# OpenBook.net
KiCad netlist of a schematic drawn in EAGLE
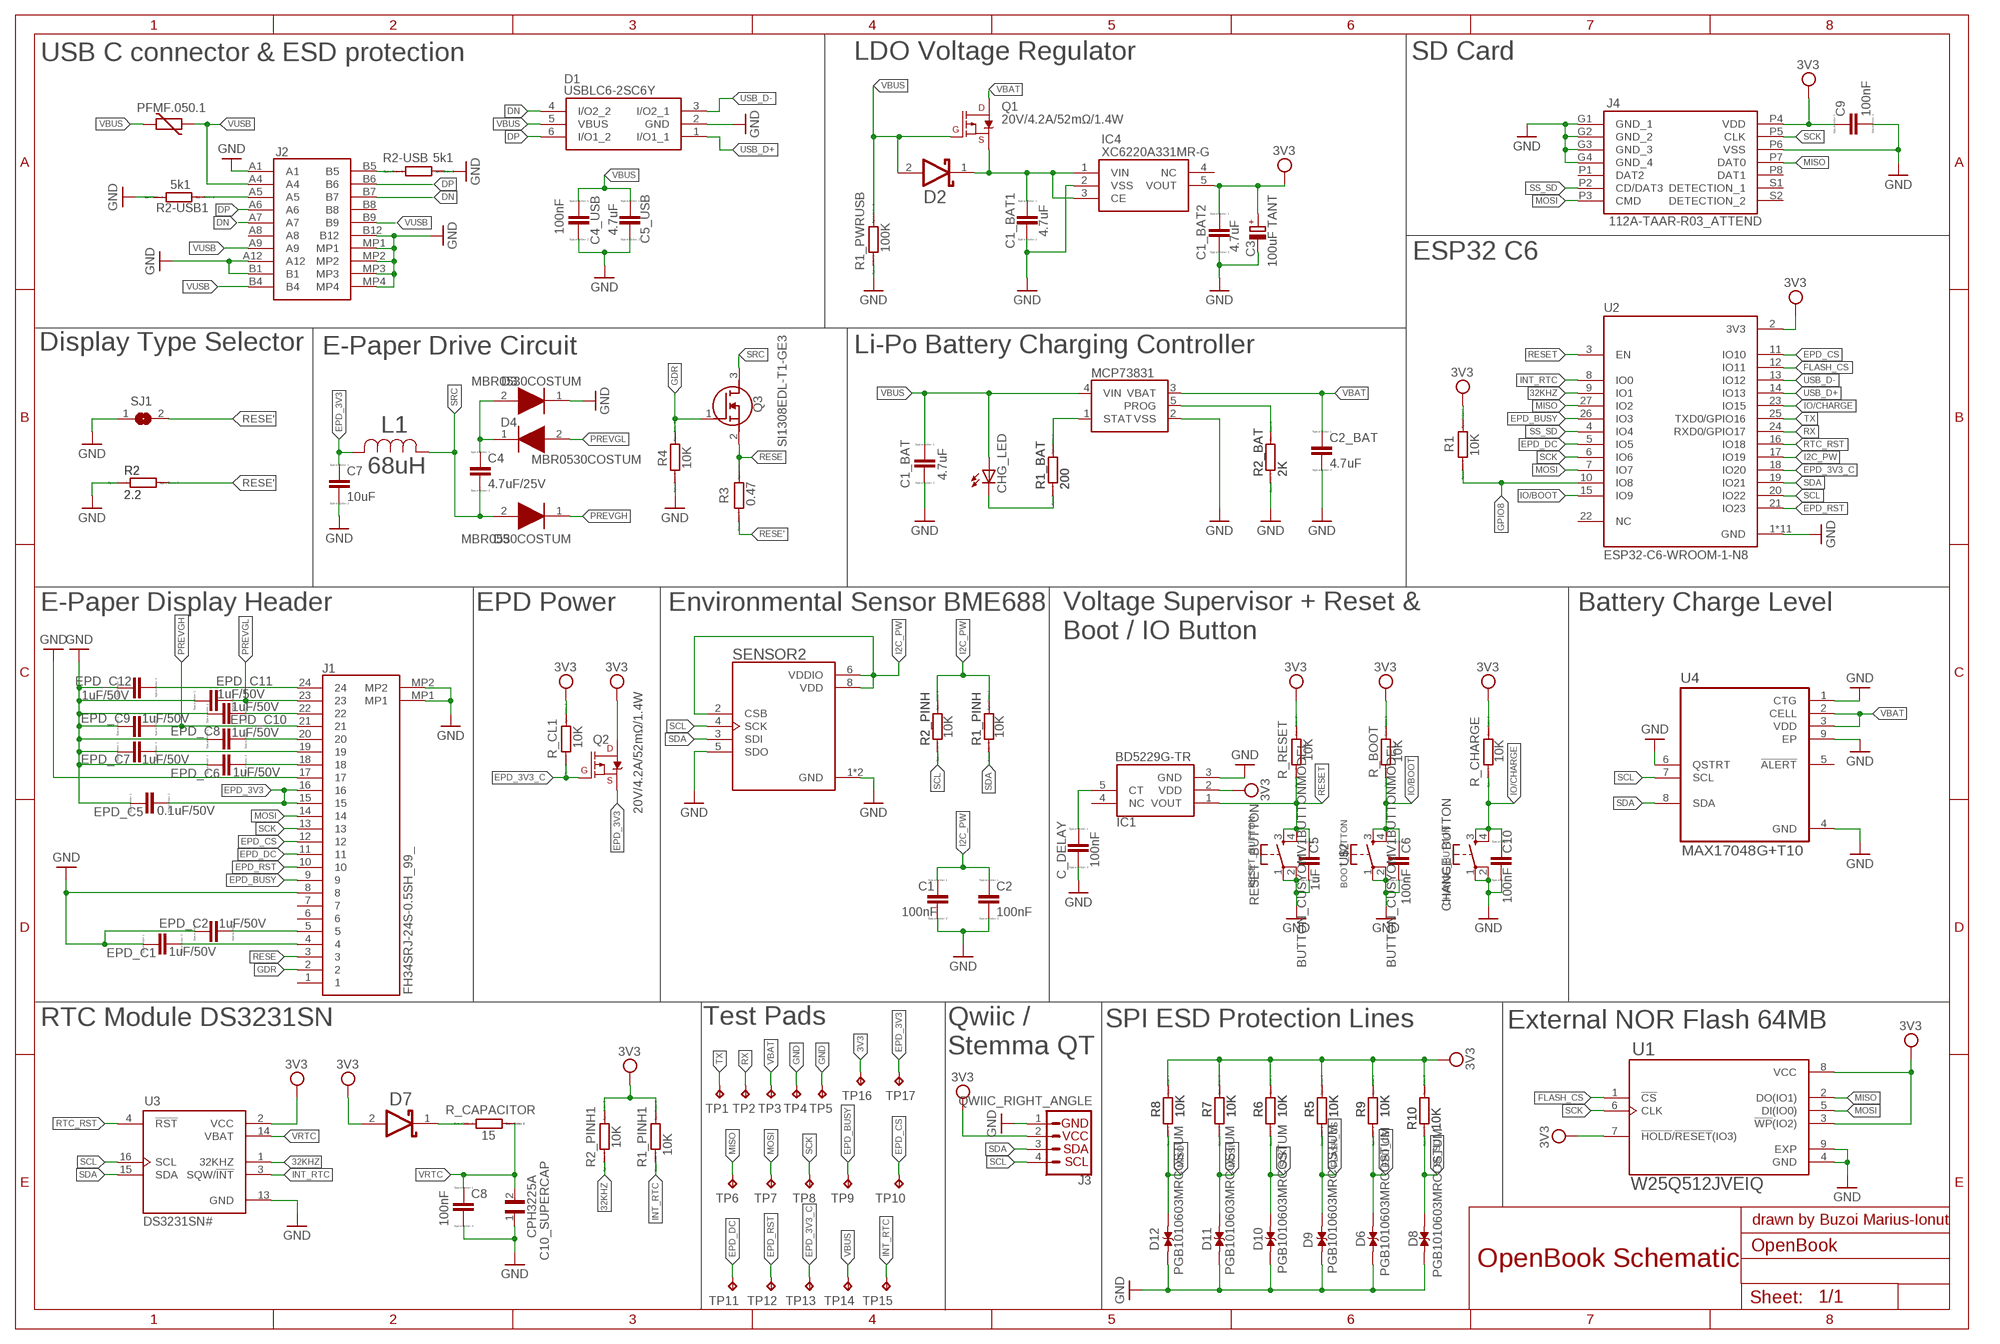
[diagram p0: schematic, sheet 1]

(export (version "E")
  (design (tool "Eeschema 10.0.6"))
  (components
    (comp (ref "C1")
      (value "100nF")
      (footprint "eagle-import:ESP32_WROVER_EAGLE-LTSPICE_C0402")
      (libsource (lib "eagle-import") (part "ESP32_WROVER_EAGLE-LTSPICE_C"))
    )
    (comp (ref "C1_BAT")
      (value "4.7uF")
      (footprint "eagle-import:ESP32_WROVER_EAGLE-LTSPICE_C0402")
      (libsource (lib "eagle-import") (part "ESP32_WROVER_EAGLE-LTSPICE_C"))
    )
    (comp (ref "C1_BAT1")
      (value "4.7uF")
      (footprint "eagle-import:ESP32_WROVER_EAGLE-LTSPICE_C0402")
      (libsource (lib "eagle-import") (part "ESP32_WROVER_EAGLE-LTSPICE_C"))
    )
    (comp (ref "C1_BAT2")
      (value "4.7uF")
      (footprint "eagle-import:ESP32_WROVER_EAGLE-LTSPICE_C0402")
      (libsource (lib "eagle-import") (part "ESP32_WROVER_EAGLE-LTSPICE_C"))
    )
    (comp (ref "C2")
      (value "100nF")
      (footprint "eagle-import:ESP32_WROVER_EAGLE-LTSPICE_C0402")
      (libsource (lib "eagle-import") (part "ESP32_WROVER_EAGLE-LTSPICE_C"))
    )
    (comp (ref "C2_BAT")
      (value "4.7uF")
      (footprint "eagle-import:ESP32_WROVER_EAGLE-LTSPICE_C0402")
      (libsource (lib "eagle-import") (part "ESP32_WROVER_EAGLE-LTSPICE_C"))
    )
    (comp (ref "C3")
      (value "100uF TANT")
      (footprint "eagle-import:RCL_CT3528")
      (libsource (lib "eagle-import") (part "RCL_CPOL-EUCT3528"))
    )
    (comp (ref "C4")
      (value "4.7uF/25V")
      (footprint "eagle-import:ESP32_WROVER_EAGLE-LTSPICE_C0402")
      (libsource (lib "eagle-import") (part "ESP32_WROVER_EAGLE-LTSPICE_C"))
    )
    (comp (ref "C4_USB")
      (value "100nF")
      (footprint "eagle-import:ESP32_WROVER_EAGLE-LTSPICE_C0402")
      (libsource (lib "eagle-import") (part "ESP32_WROVER_EAGLE-LTSPICE_C"))
    )
    (comp (ref "C5")
      (value "1uF")
      (footprint "eagle-import:ESP32_WROVER_EAGLE-LTSPICE_C0402")
      (libsource (lib "eagle-import") (part "ESP32_WROVER_EAGLE-LTSPICE_C"))
    )
    (comp (ref "C5_USB")
      (value "4.7uF")
      (footprint "eagle-import:ESP32_WROVER_EAGLE-LTSPICE_C0402")
      (libsource (lib "eagle-import") (part "ESP32_WROVER_EAGLE-LTSPICE_C"))
    )
    (comp (ref "C6")
      (value "100nF")
      (footprint "eagle-import:ESP32_WROVER_EAGLE-LTSPICE_C0402")
      (libsource (lib "eagle-import") (part "ESP32_WROVER_EAGLE-LTSPICE_C"))
    )
    (comp (ref "C7")
      (value "10uF")
      (footprint "eagle-import:ESP32_WROVER_EAGLE-LTSPICE_C0402")
      (libsource (lib "eagle-import") (part "ESP32_WROVER_EAGLE-LTSPICE_C"))
    )
    (comp (ref "C8")
      (value "100nF")
      (footprint "eagle-import:ESP32_WROVER_EAGLE-LTSPICE_C0402")
      (libsource (lib "eagle-import") (part "ESP32_WROVER_EAGLE-LTSPICE_C"))
    )
    (comp (ref "C9")
      (value "100nF")
      (footprint "eagle-import:ESP32_WROVER_EAGLE-LTSPICE_C0402")
      (libsource (lib "eagle-import") (part "ESP32_WROVER_EAGLE-LTSPICE_C"))
    )
    (comp (ref "C10")
      (value "100nF")
      (footprint "eagle-import:ESP32_WROVER_EAGLE-LTSPICE_C0402")
      (libsource (lib "eagle-import") (part "ESP32_WROVER_EAGLE-LTSPICE_C"))
    )
    (comp (ref "C10_SUPERCAP")
      (value "CPH3225A")
      (footprint "eagle-import:CAPCP3225X100N")
      (fields (field (name "MF") "Seiko Instruments"))
      (libsource (lib "eagle-import") (part "CPH3225A"))
    )
    (comp (ref "CHANGE_BUTTON")
      (value "BUTTON_CUSYOMV1BUTTONMODEL")
      (footprint "eagle-import:MYBUTTON")
      (libsource (lib "eagle-import") (part "BUTTON_CUSYOMV1BUTTONMODEL"))
    )
    (comp (ref "CHG_LED")
      (value "ADAFRUIT_LEDCHIP-LED0603")
      (footprint "eagle-import:ADAFRUIT_CHIP-LED0603")
      (libsource (lib "eagle-import") (part "ADAFRUIT_LEDCHIP-LED0603"))
    )
    (comp (ref "C_DELAY")
      (value "100nF")
      (footprint "eagle-import:ESP32_WROVER_EAGLE-LTSPICE_C0402")
      (libsource (lib "eagle-import") (part "ESP32_WROVER_EAGLE-LTSPICE_C"))
    )
    (comp (ref "D1")
      (value "USBLC6-2SC6Y")
      (footprint "eagle-import:SOT95P280X145-6N")
      (fields (field (name "MF") "STMicroelectronics"))
      (libsource (lib "eagle-import") (part "USBLC6-2SC6Y"))
    )
    (comp (ref "D2")
      (value "ESP32_WROVER_AVX---SD0805S020S1R0_AVX_SD0805S020S1R0_0_0AVX_SD0805S020S1R0_0_0")
      (footprint "eagle-import:ESP32_WROVER_AVX---SD0805S020S1R0_AVX_SD0805S020S1R0_0")
      (fields
        (field (name "DIGIKEY_PART_NUMBER") "478-7800-1-ND")
        (field (name "MF") "AVX")
        (field (name "MOUSER_PART_NUMBER") "581-SD0805S020S1R0")
      )
      (libsource (lib "eagle-import") (part "ESP32_WROVER_AVX---SD0805S020S1R0_AVX_SD0805S020S1R0_0_0AVX_SD0805S020S1R0_0_0"))
    )
    (comp (ref "D3")
      (value "MBR0530COSTUM")
      (footprint "eagle-import:SOD3716X135N")
      (libsource (lib "eagle-import") (part "MBR0530COSTUM"))
    )
    (comp (ref "D4")
      (value "MBR0530COSTUM")
      (footprint "eagle-import:SOD3716X135N")
      (libsource (lib "eagle-import") (part "MBR0530COSTUM"))
    )
    (comp (ref "D5")
      (value "MBR0530COSTUM")
      (footprint "eagle-import:SOD3716X135N")
      (libsource (lib "eagle-import") (part "MBR0530COSTUM"))
    )
    (comp (ref "D6")
      (value "PGB1010603MRCOSTUM")
      (footprint "eagle-import:DIOC1608X36N")
      (libsource (lib "eagle-import") (part "PGB1010603MRCOSTUM"))
    )
    (comp (ref "D7")
      (value "ESP32_WROVER_AVX---SD0805S020S1R0_AVX_SD0805S020S1R0_0_0AVX_SD0805S020S1R0_0_0")
      (footprint "eagle-import:ESP32_WROVER_AVX---SD0805S020S1R0_AVX_SD0805S020S1R0_0")
      (fields
        (field (name "DIGIKEY_PART_NUMBER") "478-7800-1-ND")
        (field (name "MF") "AVX")
        (field (name "MOUSER_PART_NUMBER") "581-SD0805S020S1R0")
      )
      (libsource (lib "eagle-import") (part "ESP32_WROVER_AVX---SD0805S020S1R0_AVX_SD0805S020S1R0_0_0AVX_SD0805S020S1R0_0_0"))
    )
    (comp (ref "D8")
      (value "PGB1010603MRCOSTUM")
      (footprint "eagle-import:DIOC1608X36N")
      (libsource (lib "eagle-import") (part "PGB1010603MRCOSTUM"))
    )
    (comp (ref "D9")
      (value "PGB1010603MRCOSTUM")
      (footprint "eagle-import:DIOC1608X36N")
      (libsource (lib "eagle-import") (part "PGB1010603MRCOSTUM"))
    )
    (comp (ref "D10")
      (value "PGB1010603MRCOSTUM")
      (footprint "eagle-import:DIOC1608X36N")
      (libsource (lib "eagle-import") (part "PGB1010603MRCOSTUM"))
    )
    (comp (ref "D11")
      (value "PGB1010603MRCOSTUM")
      (footprint "eagle-import:DIOC1608X36N")
      (libsource (lib "eagle-import") (part "PGB1010603MRCOSTUM"))
    )
    (comp (ref "D12")
      (value "PGB1010603MRCOSTUM")
      (footprint "eagle-import:DIOC1608X36N")
      (libsource (lib "eagle-import") (part "PGB1010603MRCOSTUM"))
    )
    (comp (ref "EPD_C1")
      (value "1uF/50V")
      (footprint "eagle-import:ESP32_WROVER_EAGLE-LTSPICE_C0402")
      (libsource (lib "eagle-import") (part "ESP32_WROVER_EAGLE-LTSPICE_C"))
    )
    (comp (ref "EPD_C2")
      (value "1uF/50V")
      (footprint "eagle-import:ESP32_WROVER_EAGLE-LTSPICE_C0402")
      (libsource (lib "eagle-import") (part "ESP32_WROVER_EAGLE-LTSPICE_C"))
    )
    (comp (ref "EPD_C5")
      (value "0.1uF/50V")
      (footprint "eagle-import:ESP32_WROVER_EAGLE-LTSPICE_C0402")
      (libsource (lib "eagle-import") (part "ESP32_WROVER_EAGLE-LTSPICE_C"))
    )
    (comp (ref "EPD_C6")
      (value "1uF/50V")
      (footprint "eagle-import:ESP32_WROVER_EAGLE-LTSPICE_C0402")
      (libsource (lib "eagle-import") (part "ESP32_WROVER_EAGLE-LTSPICE_C"))
    )
    (comp (ref "EPD_C7")
      (value "1uF/50V")
      (footprint "eagle-import:ESP32_WROVER_EAGLE-LTSPICE_C0402")
      (libsource (lib "eagle-import") (part "ESP32_WROVER_EAGLE-LTSPICE_C"))
    )
    (comp (ref "EPD_C8")
      (value "1uF/50V")
      (footprint "eagle-import:ESP32_WROVER_EAGLE-LTSPICE_C0402")
      (libsource (lib "eagle-import") (part "ESP32_WROVER_EAGLE-LTSPICE_C"))
    )
    (comp (ref "EPD_C9")
      (value "1uF/50V")
      (footprint "eagle-import:ESP32_WROVER_EAGLE-LTSPICE_C0402")
      (libsource (lib "eagle-import") (part "ESP32_WROVER_EAGLE-LTSPICE_C"))
    )
    (comp (ref "EPD_C10")
      (value "1uF/50V")
      (footprint "eagle-import:ESP32_WROVER_EAGLE-LTSPICE_C0402")
      (libsource (lib "eagle-import") (part "ESP32_WROVER_EAGLE-LTSPICE_C"))
    )
    (comp (ref "EPD_C11")
      (value "1uF/50V")
      (footprint "eagle-import:ESP32_WROVER_EAGLE-LTSPICE_C0402")
      (libsource (lib "eagle-import") (part "ESP32_WROVER_EAGLE-LTSPICE_C"))
    )
    (comp (ref "EPD_C12")
      (value "1uF/50V")
      (footprint "eagle-import:ESP32_WROVER_EAGLE-LTSPICE_C0402")
      (libsource (lib "eagle-import") (part "ESP32_WROVER_EAGLE-LTSPICE_C"))
    )
    (comp (ref "IC1")
      (value "BD5229G-TR")
      (footprint "eagle-import:SOT95P280X125-5N")
      (fields (field (name "MOUSER_PART_NUMBER") "755-BD5229G-TR"))
      (libsource (lib "eagle-import") (part "BD5229G-TR"))
    )
    (comp (ref "IC4")
      (value "XC6220A331MR-G")
      (footprint "eagle-import:SOT95P280X120-5N")
      (fields (field (name "MOUSER_PART_NUMBER") "865-XC6220A331MR-G"))
      (libsource (lib "eagle-import") (part "XC6220A331MR-G"))
    )
    (comp (ref "J1")
      (value "FH34SRJ-24S-0.5SH_99_")
      (footprint "eagle-import:FH34SRJ24S05SH99")
      (fields
        (field (name "MANUFACTURER_PART_NUMBER") "FH34SRJ-24S-0.5SH(99)")
        (field (name "MOUSER_PART_NUMBER") "798-FH34SRJ24S05SH99")
      )
      (libsource (lib "eagle-import") (part "FH34SRJ-24S-0.5SH_99_"))
    )
    (comp (ref "J2")
      (value "SAMACSYS_PARTS_USB4110-GF-A")
      (footprint "eagle-import:SAMACSYS_PARTS_USB4110GFA")
      (fields
        (field (name "MANUFACTURER_PART_NUMBER") "USB4110-GF-A")
        (field (name "MOUSER_PART_NUMBER") "640-USB4110-GF-A")
      )
      (libsource (lib "eagle-import") (part "SAMACSYS_PARTS_USB4110-GF-A"))
    )
    (comp (ref "J3")
      (value "QWIIC_RIGHT_ANGLE")
      (footprint "eagle-import:JST04_1MM_RA")
      (libsource (lib "eagle-import") (part "QWIIC_CONNECTORJS-1MM"))
    )
    (comp (ref "J4")
      (value "112A-TAAR-R03_ATTEND")
      (footprint "eagle-import:112ATAARR03ATTEND")
      (fields (field (name "MANUFACTURER_PART_NUMBER") "112A-TAAR-R03 ATTEND"))
      (libsource (lib "eagle-import") (part "112A-TAAR-R03_ATTEND"))
    )
    (comp (ref "L1")
      (value "68uH")
      (footprint "eagle-import:IND_4828-WE-TPC_WRE")
      (fields
        (field (name "MANUFACTURER_PART_NUMBER") "744043680")
        (field (name "COPYRIGHT") "Copyright (C) 2024 Ultra Librarian. All rights reserved.")
      )
      (libsource (lib "eagle-import") (part "744043680IND_4828-WE-TPC_WRE"))
    )
    (comp (ref "MCP73831")
      (value "ESP32_WROVER_SPARKFUN-IC-POWER_MCP73831")
      (footprint "eagle-import:ESP32_WROVER_SPARKFUN-IC-POWER_SOT23-5")
      (libsource (lib "eagle-import") (part "ESP32_WROVER_SPARKFUN-IC-POWER_MCP73831"))
    )
    (comp (ref "PFMF.050.1")
      (value "ESP32C6_VARISTORCN1812")
      (footprint "eagle-import:ESP32C6_VARISTOR_CT_CN1812")
      (libsource (lib "eagle-import") (part "ESP32C6_VARISTORCN1812"))
    )
    (comp (ref "Q1")
      (value "20V/4.2A/52mΩ/1.4W")
      (footprint "eagle-import:ESP32_WROVER_SPARKFUN-DISCRETESEMI_SOT23-3")
      (libsource (lib "eagle-import") (part "ESP32_WROVER_SPARKFUN-DISCRETESEMI_MOSFET_PCH-DMG2305UX-7"))
    )
    (comp (ref "Q2")
      (value "20V/4.2A/52mΩ/1.4W")
      (footprint "eagle-import:ESP32_WROVER_SPARKFUN-DISCRETESEMI_SOT23-3")
      (libsource (lib "eagle-import") (part "ESP32_WROVER_SPARKFUN-DISCRETESEMI_MOSFET_PCH-DMG2305UX-7"))
    )
    (comp (ref "Q3")
      (value "SI1308EDL-T1-GE3")
      (footprint "eagle-import:SOT65P210X110-3N")
      (fields (field (name "MF") "Vishay Siliconix"))
      (libsource (lib "eagle-import") (part "SI1308EDL-T1-GE3"))
    )
    (comp (ref "R1")
      (value "10K")
      (footprint "eagle-import:ESP32_WROVER_EAGLE-LTSPICE_R0402")
      (libsource (lib "eagle-import") (part "ESP32_WROVER_EAGLE-LTSPICE_R"))
    )
    (comp (ref "R1_BAT")
      (value "200")
      (footprint "eagle-import:ESP32_WROVER_EAGLE-LTSPICE_R0402")
      (libsource (lib "eagle-import") (part "ESP32_WROVER_EAGLE-LTSPICE_R"))
    )
    (comp (ref "R1_PINH")
      (value "10K")
      (footprint "eagle-import:ESP32_WROVER_EAGLE-LTSPICE_R0402")
      (libsource (lib "eagle-import") (part "ESP32_WROVER_EAGLE-LTSPICE_R"))
    )
    (comp (ref "R1_PINH1")
      (value "10K")
      (footprint "eagle-import:ESP32_WROVER_EAGLE-LTSPICE_R0402")
      (libsource (lib "eagle-import") (part "ESP32_WROVER_EAGLE-LTSPICE_R"))
    )
    (comp (ref "R1_PWRUSB")
      (value "100K")
      (footprint "eagle-import:ESP32_WROVER_EAGLE-LTSPICE_R0402")
      (libsource (lib "eagle-import") (part "ESP32_WROVER_EAGLE-LTSPICE_R"))
    )
    (comp (ref "R2")
      (value "2.2")
      (footprint "eagle-import:ESP32_WROVER_EAGLE-LTSPICE_R0402")
      (libsource (lib "eagle-import") (part "ESP32_WROVER_EAGLE-LTSPICE_R"))
    )
    (comp (ref "R2-USB")
      (value "5k1")
      (footprint "eagle-import:ESP32_WROVER_EAGLE-LTSPICE_R0402")
      (libsource (lib "eagle-import") (part "ESP32_WROVER_EAGLE-LTSPICE_R"))
    )
    (comp (ref "R2-USB1")
      (value "5k1")
      (footprint "eagle-import:ESP32_WROVER_EAGLE-LTSPICE_R0402")
      (libsource (lib "eagle-import") (part "ESP32_WROVER_EAGLE-LTSPICE_R"))
    )
    (comp (ref "R2_BAT")
      (value "2K")
      (footprint "eagle-import:ESP32_WROVER_EAGLE-LTSPICE_R0402")
      (libsource (lib "eagle-import") (part "ESP32_WROVER_EAGLE-LTSPICE_R"))
    )
    (comp (ref "R2_PINH")
      (value "10K")
      (footprint "eagle-import:ESP32_WROVER_EAGLE-LTSPICE_R0402")
      (libsource (lib "eagle-import") (part "ESP32_WROVER_EAGLE-LTSPICE_R"))
    )
    (comp (ref "R2_PINH1")
      (value "10K")
      (footprint "eagle-import:ESP32_WROVER_EAGLE-LTSPICE_R0402")
      (libsource (lib "eagle-import") (part "ESP32_WROVER_EAGLE-LTSPICE_R"))
    )
    (comp (ref "R3")
      (value "0.47")
      (footprint "eagle-import:ESP32_WROVER_EAGLE-LTSPICE_R0402")
      (libsource (lib "eagle-import") (part "ESP32_WROVER_EAGLE-LTSPICE_R"))
    )
    (comp (ref "R4")
      (value "10K")
      (footprint "eagle-import:ESP32_WROVER_EAGLE-LTSPICE_R0402")
      (libsource (lib "eagle-import") (part "ESP32_WROVER_EAGLE-LTSPICE_R"))
    )
    (comp (ref "R5")
      (value "10K")
      (footprint "eagle-import:ESP32_WROVER_EAGLE-LTSPICE_R0402")
      (libsource (lib "eagle-import") (part "ESP32_WROVER_EAGLE-LTSPICE_R"))
    )
    (comp (ref "R6")
      (value "10K")
      (footprint "eagle-import:ESP32_WROVER_EAGLE-LTSPICE_R0402")
      (libsource (lib "eagle-import") (part "ESP32_WROVER_EAGLE-LTSPICE_R"))
    )
    (comp (ref "R7")
      (value "10K")
      (footprint "eagle-import:ESP32_WROVER_EAGLE-LTSPICE_R0402")
      (libsource (lib "eagle-import") (part "ESP32_WROVER_EAGLE-LTSPICE_R"))
    )
    (comp (ref "R8")
      (value "10K")
      (footprint "eagle-import:ESP32_WROVER_EAGLE-LTSPICE_R0402")
      (libsource (lib "eagle-import") (part "ESP32_WROVER_EAGLE-LTSPICE_R"))
    )
    (comp (ref "R9")
      (value "10K")
      (footprint "eagle-import:ESP32_WROVER_EAGLE-LTSPICE_R0402")
      (libsource (lib "eagle-import") (part "ESP32_WROVER_EAGLE-LTSPICE_R"))
    )
    (comp (ref "R10")
      (value "10K")
      (footprint "eagle-import:ESP32_WROVER_EAGLE-LTSPICE_R0402")
      (libsource (lib "eagle-import") (part "ESP32_WROVER_EAGLE-LTSPICE_R"))
    )
    (comp (ref "RESET_BUTTON")
      (value "BUTTON_CUSYOMV1BUTTONMODEL")
      (footprint "eagle-import:MYBUTTON")
      (libsource (lib "eagle-import") (part "BUTTON_CUSYOMV1BUTTONMODEL"))
    )
    (comp (ref "R_BOOT")
      (value "10K")
      (footprint "eagle-import:ESP32_WROVER_EAGLE-LTSPICE_R0402")
      (libsource (lib "eagle-import") (part "ESP32_WROVER_EAGLE-LTSPICE_R"))
    )
    (comp (ref "R_CAPACITOR")
      (value "15")
      (footprint "eagle-import:ESP32_WROVER_EAGLE-LTSPICE_R0402")
      (libsource (lib "eagle-import") (part "ESP32_WROVER_EAGLE-LTSPICE_R"))
    )
    (comp (ref "R_CHARGE")
      (value "10K")
      (footprint "eagle-import:ESP32_WROVER_EAGLE-LTSPICE_R0402")
      (libsource (lib "eagle-import") (part "ESP32_WROVER_EAGLE-LTSPICE_R"))
    )
    (comp (ref "R_CL1")
      (value "10K")
      (footprint "eagle-import:ESP32_WROVER_EAGLE-LTSPICE_R0402")
      (libsource (lib "eagle-import") (part "ESP32_WROVER_EAGLE-LTSPICE_R"))
    )
    (comp (ref "R_RESET")
      (value "10K")
      (footprint "eagle-import:ESP32_WROVER_EAGLE-LTSPICE_R0402")
      (libsource (lib "eagle-import") (part "ESP32_WROVER_EAGLE-LTSPICE_R"))
    )
    (comp (ref "SENSOR2")
      (value "ESP32_WROVER_BME680_BME680")
      (footprint "eagle-import:ESP32_WROVER_BME680_PSON80P300X300X100-8N")
      (fields (field (name "MF") "Bosch Sensortec") (field (name "MP") "BME680"))
      (libsource (lib "eagle-import") (part "ESP32_WROVER_BME680_BME680"))
    )
    (comp (ref "SJ1") (value "SJ") (footprint "eagle-import:SJ") (libsource (lib "eagle-import") (part "SJ")))
    (comp (ref "TP1")
      (value "TP")
      (footprint "eagle-import:TP20R")
      (libsource (lib "eagle-import") (part "TP"))
    )
    (comp (ref "TP2")
      (value "TP")
      (footprint "eagle-import:TP20R")
      (libsource (lib "eagle-import") (part "TP"))
    )
    (comp (ref "TP3")
      (value "TP")
      (footprint "eagle-import:TP20R")
      (libsource (lib "eagle-import") (part "TP"))
    )
    (comp (ref "TP4")
      (value "TP")
      (footprint "eagle-import:TP20R")
      (libsource (lib "eagle-import") (part "TP"))
    )
    (comp (ref "TP5")
      (value "TP")
      (footprint "eagle-import:TP20R")
      (libsource (lib "eagle-import") (part "TP"))
    )
    (comp (ref "TP6")
      (value "TP")
      (footprint "eagle-import:TP20R")
      (libsource (lib "eagle-import") (part "TP"))
    )
    (comp (ref "TP7")
      (value "TP")
      (footprint "eagle-import:TP20R")
      (libsource (lib "eagle-import") (part "TP"))
    )
    (comp (ref "TP8")
      (value "TP")
      (footprint "eagle-import:TP20R")
      (libsource (lib "eagle-import") (part "TP"))
    )
    (comp (ref "TP9")
      (value "TP")
      (footprint "eagle-import:TP20R")
      (libsource (lib "eagle-import") (part "TP"))
    )
    (comp (ref "TP10")
      (value "TP")
      (footprint "eagle-import:TP20R")
      (libsource (lib "eagle-import") (part "TP"))
    )
    (comp (ref "TP11")
      (value "TP")
      (footprint "eagle-import:TP20R")
      (libsource (lib "eagle-import") (part "TP"))
    )
    (comp (ref "TP12")
      (value "TP")
      (footprint "eagle-import:TP20R")
      (libsource (lib "eagle-import") (part "TP"))
    )
    (comp (ref "TP13")
      (value "TP")
      (footprint "eagle-import:TP20R")
      (libsource (lib "eagle-import") (part "TP"))
    )
    (comp (ref "TP14")
      (value "TP")
      (footprint "eagle-import:TP20R")
      (libsource (lib "eagle-import") (part "TP"))
    )
    (comp (ref "TP15")
      (value "TP")
      (footprint "eagle-import:TP20R")
      (libsource (lib "eagle-import") (part "TP"))
    )
    (comp (ref "TP16")
      (value "TP")
      (footprint "eagle-import:TP20R")
      (libsource (lib "eagle-import") (part "TP"))
    )
    (comp (ref "TP17")
      (value "TP")
      (footprint "eagle-import:TP20R")
      (libsource (lib "eagle-import") (part "TP"))
    )
    (comp (ref "U$2")
      (value "BUTTON_CUSYOMV1BUTTONMODEL")
      (footprint "eagle-import:MYBUTTON")
      (libsource (lib "eagle-import") (part "BUTTON_CUSYOMV1BUTTONMODEL"))
    )
    (comp (ref "U1")
      (value "W25Q512JVEIQ")
      (footprint "eagle-import:SON127P600X800X80-9N")
      (fields (field (name "MF") "Winbond Electronics"))
      (libsource (lib "eagle-import") (part "W25Q512JVEIQ"))
    )
    (comp (ref "U2")
      (value "ESP32-C6-WROOM-1-N8")
      (footprint "eagle-import:XCVR_ESP32-C6-WROOM-1-N8")
      (fields (field (name "MF") "Espressif Systems"))
      (libsource (lib "eagle-import") (part "ESP32-C6-WROOM-1-N8"))
    )
    (comp (ref "U3")
      (value "DS3231SN#")
      (footprint "eagle-import:SOIC127P1032X265-16N")
      (fields (field (name "MF") "Analog Devices"))
      (libsource (lib "eagle-import") (part "DS3231SN#"))
    )
    (comp (ref "U4")
      (value "MAX17048G+T10")
      (footprint "eagle-import:SON50P200X200X80-9N")
      (fields (field (name "MF") "Analog Devices"))
      (libsource (lib "eagle-import") (part "MAX17048G+T10"))
    )
  )
  (nets
    (net (code "1") (name "3V3") (class "Default")
      (node (ref "C1_BAT2") (pin "1") (pinfunction "1_1") (pintype "passive"))
      (node (ref "C3") (pin "+") (pinfunction "+_+") (pintype "passive"))
      (node (ref "C9") (pin "1") (pinfunction "1_1") (pintype "passive"))
      (node (ref "D7") (pin "2") (pinfunction "ANODE_2") (pintype "bidirectional"))
      (node (ref "IC1") (pin "2") (pinfunction "VDD_2") (pintype "bidirectional"))
      (node (ref "IC4") (pin "5") (pinfunction "VOUT_5") (pintype "bidirectional"))
      (node (ref "J3") (pin "2") (pinfunction "2_2") (pintype "power_in"))
      (node (ref "J4") (pin "P4") (pinfunction "VDD_P4") (pintype "bidirectional"))
      (node (ref "Q2") (pin "3") (pinfunction "D_3") (pintype "bidirectional"))
      (node (ref "R1") (pin "2") (pinfunction "2_2") (pintype "passive"))
      (node (ref "R10") (pin "2") (pinfunction "2_2") (pintype "passive"))
      (node (ref "R1_PINH1") (pin "2") (pinfunction "2_2") (pintype "passive"))
      (node (ref "R2_PINH1") (pin "2") (pinfunction "2_2") (pintype "passive"))
      (node (ref "R5") (pin "2") (pinfunction "2_2") (pintype "passive"))
      (node (ref "R6") (pin "2") (pinfunction "2_2") (pintype "passive"))
      (node (ref "R7") (pin "2") (pinfunction "2_2") (pintype "passive"))
      (node (ref "R8") (pin "2") (pinfunction "2_2") (pintype "passive"))
      (node (ref "R9") (pin "2") (pinfunction "2_2") (pintype "passive"))
      (node (ref "R_BOOT") (pin "2") (pinfunction "2_2") (pintype "passive"))
      (node (ref "R_CHARGE") (pin "2") (pinfunction "2_2") (pintype "passive"))
      (node (ref "R_CL1") (pin "2") (pinfunction "2_2") (pintype "passive"))
      (node (ref "R_RESET") (pin "2") (pinfunction "2_2") (pintype "passive"))
      (node (ref "TP16") (pin "TP") (pinfunction "TP_TP") (pintype "input"))
      (node (ref "U1") (pin "3") (pinfunction "~{WP}(IO2)_3") (pintype "bidirectional"))
      (node (ref "U1") (pin "7") (pinfunction "~{HOLD}/~{RESET}(IO3)_7") (pintype "bidirectional"))
      (node (ref "U1") (pin "8") (pinfunction "VCC_8") (pintype "power_in"))
      (node (ref "U2") (pin "2") (pinfunction "3V3_2") (pintype "power_in"))
      (node (ref "U3") (pin "2") (pinfunction "VCC_2") (pintype "power_in"))
    )
    (net (code "2") (name "32KHZ") (class "Default")
      (node (ref "R2_PINH1") (pin "1") (pinfunction "1_1") (pintype "passive"))
      (node (ref "U2") (pin "9") (pinfunction "IO1_9") (pintype "bidirectional"))
      (node (ref "U3") (pin "1") (pinfunction "32KHZ_1") (pintype "output"))
    )
    (net (code "3") (name "DN") (class "Default")
      (node (ref "D1") (pin "4") (pinfunction "I/O2_2_4") (pintype "bidirectional"))
      (node (ref "J2") (pin "A7") (pinfunction "A7_A7") (pintype "bidirectional"))
      (node (ref "J2") (pin "B7") (pinfunction "B7_B7") (pintype "bidirectional"))
    )
    (net (code "4") (name "DP") (class "Default")
      (node (ref "D1") (pin "6") (pinfunction "I/O1_2_6") (pintype "bidirectional"))
      (node (ref "J2") (pin "A6") (pinfunction "A6_A6") (pintype "bidirectional"))
      (node (ref "J2") (pin "B6") (pinfunction "B6_B6") (pintype "bidirectional"))
    )
    (net (code "5") (name "EPD_3V3") (class "Default")
      (node (ref "C7") (pin "1") (pinfunction "1_1") (pintype "passive"))
      (node (ref "EPD_C5") (pin "2") (pinfunction "2_2") (pintype "passive"))
      (node (ref "J1") (pin "15") (pinfunction "15_15") (pintype "bidirectional"))
      (node (ref "J1") (pin "16") (pinfunction "16_16") (pintype "bidirectional"))
      (node (ref "L1") (pin "2") (pinfunction "2_2") (pintype "passive"))
      (node (ref "Q2") (pin "2") (pinfunction "S_2") (pintype "bidirectional"))
      (node (ref "TP17") (pin "TP") (pinfunction "TP_TP") (pintype "input"))
    )
    (net (code "6") (name "EPD_3V3_C") (class "Default")
      (node (ref "Q2") (pin "1") (pinfunction "G_1") (pintype "bidirectional"))
      (node (ref "R_CL1") (pin "1") (pinfunction "1_1") (pintype "passive"))
      (node (ref "TP13") (pin "TP") (pinfunction "TP_TP") (pintype "input"))
      (node (ref "U2") (pin "18") (pinfunction "IO20_18") (pintype "bidirectional"))
    )
    (net (code "7") (name "EPD_BUSY") (class "Default")
      (node (ref "J1") (pin "9") (pinfunction "9_9") (pintype "bidirectional"))
      (node (ref "TP9") (pin "TP") (pinfunction "TP_TP") (pintype "input"))
      (node (ref "U2") (pin "26") (pinfunction "IO3_26") (pintype "bidirectional"))
    )
    (net (code "8") (name "EPD_CS") (class "Default")
      (node (ref "D6") (pin "2") (pinfunction "2_2") (pintype "passive"))
      (node (ref "J1") (pin "12") (pinfunction "12_12") (pintype "bidirectional"))
      (node (ref "R9") (pin "1") (pinfunction "1_1") (pintype "passive"))
      (node (ref "TP10") (pin "TP") (pinfunction "TP_TP") (pintype "input"))
      (node (ref "U2") (pin "11") (pinfunction "IO10_11") (pintype "bidirectional"))
    )
    (net (code "9") (name "EPD_DC") (class "Default")
      (node (ref "J1") (pin "11") (pinfunction "11_11") (pintype "bidirectional"))
      (node (ref "TP11") (pin "TP") (pinfunction "TP_TP") (pintype "input"))
      (node (ref "U2") (pin "5") (pinfunction "IO5_5") (pintype "bidirectional"))
    )
    (net (code "10") (name "EPD_RST") (class "Default")
      (node (ref "J1") (pin "10") (pinfunction "10_10") (pintype "bidirectional"))
      (node (ref "TP12") (pin "TP") (pinfunction "TP_TP") (pintype "input"))
      (node (ref "U2") (pin "21") (pinfunction "IO23_21") (pintype "bidirectional"))
    )
    (net (code "11") (name "FLASH_CS") (class "Default")
      (node (ref "D9") (pin "2") (pinfunction "2_2") (pintype "passive"))
      (node (ref "R5") (pin "1") (pinfunction "1_1") (pintype "passive"))
      (node (ref "U1") (pin "1") (pinfunction "~{CS}_1") (pintype "input"))
      (node (ref "U2") (pin "12") (pinfunction "IO11_12") (pintype "bidirectional"))
    )
    (net (code "12") (name "GDR") (class "Default")
      (node (ref "J1") (pin "2") (pinfunction "2_2") (pintype "bidirectional"))
      (node (ref "Q3") (pin "1") (pinfunction "G_1") (pintype "bidirectional"))
      (node (ref "R4") (pin "2") (pinfunction "2_2") (pintype "passive"))
    )
    (net (code "13") (name "GND") (class "Default")
      (node (ref "C1") (pin "2") (pinfunction "2_2") (pintype "passive"))
      (node (ref "C10") (pin "2") (pinfunction "2_2") (pintype "passive"))
      (node (ref "C10_SUPERCAP") (pin "1") (pinfunction "1_1") (pintype "passive"))
      (node (ref "C1_BAT") (pin "2") (pinfunction "2_2") (pintype "passive"))
      (node (ref "C1_BAT1") (pin "2") (pinfunction "2_2") (pintype "passive"))
      (node (ref "C1_BAT2") (pin "2") (pinfunction "2_2") (pintype "passive"))
      (node (ref "C2") (pin "2") (pinfunction "2_2") (pintype "passive"))
      (node (ref "C2_BAT") (pin "2") (pinfunction "2_2") (pintype "passive"))
      (node (ref "C3") (pin "-") (pinfunction "-_-") (pintype "passive"))
      (node (ref "C4_USB") (pin "2") (pinfunction "2_2") (pintype "passive"))
      (node (ref "C5") (pin "2") (pinfunction "2_2") (pintype "passive"))
      (node (ref "C5_USB") (pin "2") (pinfunction "2_2") (pintype "passive"))
      (node (ref "C6") (pin "2") (pinfunction "2_2") (pintype "passive"))
      (node (ref "C7") (pin "2") (pinfunction "2_2") (pintype "passive"))
      (node (ref "C8") (pin "2") (pinfunction "2_2") (pintype "passive"))
      (node (ref "C9") (pin "2") (pinfunction "2_2") (pintype "passive"))
      (node (ref "CHANGE_BUTTON") (pin "1") (pinfunction "1_1") (pintype "passive"))
      (node (ref "CHANGE_BUTTON") (pin "2") (pinfunction "2_2") (pintype "passive"))
      (node (ref "C_DELAY") (pin "2") (pinfunction "2_2") (pintype "passive"))
      (node (ref "D1") (pin "2") (pinfunction "GND_2") (pintype "bidirectional"))
      (node (ref "D10") (pin "1") (pinfunction "1_1") (pintype "passive"))
      (node (ref "D11") (pin "1") (pinfunction "1_1") (pintype "passive"))
      (node (ref "D12") (pin "1") (pinfunction "1_1") (pintype "passive"))
      (node (ref "D3") (pin "1") (pinfunction "K_1") (pintype "bidirectional"))
      (node (ref "D6") (pin "1") (pinfunction "1_1") (pintype "passive"))
      (node (ref "D8") (pin "1") (pinfunction "1_1") (pintype "passive"))
      (node (ref "D9") (pin "1") (pinfunction "1_1") (pintype "passive"))
      (node (ref "EPD_C1") (pin "1") (pinfunction "1_1") (pintype "passive"))
      (node (ref "EPD_C10") (pin "1") (pinfunction "1_1") (pintype "passive"))
      (node (ref "EPD_C11") (pin "1") (pinfunction "1_1") (pintype "passive"))
      (node (ref "EPD_C12") (pin "1") (pinfunction "1_1") (pintype "passive"))
      (node (ref "EPD_C2") (pin "1") (pinfunction "1_1") (pintype "passive"))
      (node (ref "EPD_C5") (pin "1") (pinfunction "1_1") (pintype "passive"))
      (node (ref "EPD_C6") (pin "1") (pinfunction "1_1") (pintype "passive"))
      (node (ref "EPD_C7") (pin "1") (pinfunction "1_1") (pintype "passive"))
      (node (ref "EPD_C8") (pin "1") (pinfunction "1_1") (pintype "passive"))
      (node (ref "EPD_C9") (pin "1") (pinfunction "1_1") (pintype "passive"))
      (node (ref "IC1") (pin "3") (pinfunction "GND_3") (pintype "bidirectional"))
      (node (ref "IC4") (pin "2") (pinfunction "VSS_2") (pintype "bidirectional"))
      (node (ref "J1") (pin "17") (pinfunction "17_17") (pintype "bidirectional"))
      (node (ref "J1") (pin "8") (pinfunction "8_8") (pintype "bidirectional"))
      (node (ref "J1") (pin "MP1") (pinfunction "MP1_MP1") (pintype "bidirectional"))
      (node (ref "J1") (pin "MP2") (pinfunction "MP2_MP2") (pintype "bidirectional"))
      (node (ref "J2") (pin "A1") (pinfunction "A1_A1") (pintype "bidirectional"))
      (node (ref "J2") (pin "A12") (pinfunction "A12_A12") (pintype "bidirectional"))
      (node (ref "J2") (pin "B1") (pinfunction "B1_B1") (pintype "bidirectional"))
      (node (ref "J2") (pin "B12") (pinfunction "B12_B12") (pintype "bidirectional"))
      (node (ref "J2") (pin "MP1") (pinfunction "MP1_MP1") (pintype "bidirectional"))
      (node (ref "J2") (pin "MP2") (pinfunction "MP2_MP2") (pintype "bidirectional"))
      (node (ref "J2") (pin "MP3") (pinfunction "MP3_MP3") (pintype "bidirectional"))
      (node (ref "J2") (pin "MP4") (pinfunction "MP4_MP4") (pintype "bidirectional"))
      (node (ref "J3") (pin "1") (pinfunction "1_1") (pintype "power_in"))
      (node (ref "J4") (pin "G1") (pinfunction "GND_1_G1") (pintype "bidirectional"))
      (node (ref "J4") (pin "G2") (pinfunction "GND_2_G2") (pintype "bidirectional"))
      (node (ref "J4") (pin "G3") (pinfunction "GND_3_G3") (pintype "bidirectional"))
      (node (ref "J4") (pin "G4") (pinfunction "GND_4_G4") (pintype "bidirectional"))
      (node (ref "J4") (pin "P6") (pinfunction "VSS_P6") (pintype "bidirectional"))
      (node (ref "MCP73831") (pin "2") (pinfunction "VSS_2") (pintype "power_in"))
      (node (ref "R1_PWRUSB") (pin "1") (pinfunction "1_1") (pintype "passive"))
      (node (ref "R2") (pin "1") (pinfunction "1_1") (pintype "passive"))
      (node (ref "R2-USB") (pin "2") (pinfunction "2_2") (pintype "passive"))
      (node (ref "R2-USB1") (pin "1") (pinfunction "1_1") (pintype "passive"))
      (node (ref "R2_BAT") (pin "1") (pinfunction "1_1") (pintype "passive"))
      (node (ref "R4") (pin "1") (pinfunction "1_1") (pintype "passive"))
      (node (ref "RESET_BUTTON") (pin "1") (pinfunction "1_1") (pintype "passive"))
      (node (ref "RESET_BUTTON") (pin "2") (pinfunction "2_2") (pintype "passive"))
      (node (ref "SENSOR2") (pin "1") (pinfunction "GND_1") (pintype "power_in"))
      (node (ref "SENSOR2") (pin "5") (pinfunction "SDO_5") (pintype "bidirectional"))
      (node (ref "SENSOR2") (pin "7") (pinfunction "GND_7") (pintype "power_in"))
      (node (ref "SJ1") (pin "1") (pinfunction "1_1") (pintype "passive"))
      (node (ref "TP4") (pin "TP") (pinfunction "TP_TP") (pintype "input"))
      (node (ref "TP5") (pin "TP") (pinfunction "TP_TP") (pintype "input"))
      (node (ref "U$2") (pin "1") (pinfunction "1_1") (pintype "passive"))
      (node (ref "U$2") (pin "2") (pinfunction "2_2") (pintype "passive"))
      (node (ref "U1") (pin "4") (pinfunction "GND_4") (pintype "power_in"))
      (node (ref "U1") (pin "9") (pinfunction "EXP_9") (pintype "passive"))
      (node (ref "U2") (pin "1") (pinfunction "GND_1") (pintype "power_in"))
      (node (ref "U2") (pin "28") (pinfunction "GND_28") (pintype "power_in"))
      (node (ref "U2") (pin "29_1") (pinfunction "GND_29_1") (pintype "power_in"))
      (node (ref "U2") (pin "29_2") (pinfunction "GND_29_2") (pintype "power_in"))
      (node (ref "U2") (pin "29_3") (pinfunction "GND_29_3") (pintype "power_in"))
      (node (ref "U2") (pin "29_4") (pinfunction "GND_29_4") (pintype "power_in"))
      (node (ref "U2") (pin "29_5") (pinfunction "GND_29_5") (pintype "power_in"))
      (node (ref "U2") (pin "29_6") (pinfunction "GND_29_6") (pintype "power_in"))
      (node (ref "U2") (pin "29_7") (pinfunction "GND_29_7") (pintype "power_in"))
      (node (ref "U2") (pin "29_8") (pinfunction "GND_29_8") (pintype "power_in"))
      (node (ref "U2") (pin "29_9") (pinfunction "GND_29_9") (pintype "power_in"))
      (node (ref "U3") (pin "13") (pinfunction "GND_13") (pintype "power_in"))
      (node (ref "U4") (pin "1") (pinfunction "CTG_1") (pintype "power_in"))
      (node (ref "U4") (pin "4") (pinfunction "GND_4") (pintype "power_in"))
      (node (ref "U4") (pin "6") (pinfunction "QSTRT_6") (pintype "input"))
      (node (ref "U4") (pin "9") (pinfunction "EP_9") (pintype "power_in"))
    )
    (net (code "14") (name "GPIO8") (class "Default")
      (node (ref "R1") (pin "1") (pinfunction "1_1") (pintype "passive"))
      (node (ref "U2") (pin "10") (pinfunction "IO8_10") (pintype "bidirectional"))
    )
    (net (code "15") (name "I2C_PW") (class "Default")
      (node (ref "C1") (pin "1") (pinfunction "1_1") (pintype "passive"))
      (node (ref "C2") (pin "1") (pinfunction "1_1") (pintype "passive"))
      (node (ref "R1_PINH") (pin "2") (pinfunction "2_2") (pintype "passive"))
      (node (ref "R2_PINH") (pin "2") (pinfunction "2_2") (pintype "passive"))
      (node (ref "SENSOR2") (pin "2") (pinfunction "CSB_2") (pintype "input"))
      (node (ref "SENSOR2") (pin "6") (pinfunction "VDDIO_6") (pintype "power_in"))
      (node (ref "SENSOR2") (pin "8") (pinfunction "VDD_8") (pintype "power_in"))
      (node (ref "U2") (pin "17") (pinfunction "IO19_17") (pintype "bidirectional"))
    )
    (net (code "16") (name "INT_RTC") (class "Default")
      (node (ref "R1_PINH1") (pin "1") (pinfunction "1_1") (pintype "passive"))
      (node (ref "TP15") (pin "TP") (pinfunction "TP_TP") (pintype "input"))
      (node (ref "U2") (pin "8") (pinfunction "IO0_8") (pintype "bidirectional"))
      (node (ref "U3") (pin "3") (pinfunction "SQW/~{INT}_3") (pintype "output"))
    )
    (net (code "17") (name "IO{slash}BOOT") (class "Default")
      (node (ref "C6") (pin "1") (pinfunction "1_1") (pintype "passive"))
      (node (ref "R_BOOT") (pin "1") (pinfunction "1_1") (pintype "passive"))
      (node (ref "U$2") (pin "3") (pinfunction "3_3") (pintype "passive"))
      (node (ref "U$2") (pin "4") (pinfunction "4_4") (pintype "passive"))
      (node (ref "U2") (pin "15") (pinfunction "IO9_15") (pintype "bidirectional"))
    )
    (net (code "18") (name "IO{slash}CHARGE") (class "Default")
      (node (ref "C10") (pin "1") (pinfunction "1_1") (pintype "passive"))
      (node (ref "CHANGE_BUTTON") (pin "3") (pinfunction "3_3") (pintype "passive"))
      (node (ref "CHANGE_BUTTON") (pin "4") (pinfunction "4_4") (pintype "passive"))
      (node (ref "R_CHARGE") (pin "1") (pinfunction "1_1") (pintype "passive"))
      (node (ref "U2") (pin "23") (pinfunction "IO15_23") (pintype "bidirectional"))
    )
    (net (code "19") (name "MISO") (class "Default")
      (node (ref "D12") (pin "2") (pinfunction "2_2") (pintype "passive"))
      (node (ref "J4") (pin "P7") (pinfunction "DAT0_P7") (pintype "bidirectional"))
      (node (ref "R8") (pin "1") (pinfunction "1_1") (pintype "passive"))
      (node (ref "TP6") (pin "TP") (pinfunction "TP_TP") (pintype "input"))
      (node (ref "U1") (pin "2") (pinfunction "DO(IO1)_2") (pintype "bidirectional"))
      (node (ref "U2") (pin "27") (pinfunction "IO2_27") (pintype "bidirectional"))
    )
    (net (code "20") (name "MOSI") (class "Default")
      (node (ref "D11") (pin "2") (pinfunction "2_2") (pintype "passive"))
      (node (ref "J1") (pin "14") (pinfunction "14_14") (pintype "bidirectional"))
      (node (ref "J4") (pin "P3") (pinfunction "CMD_P3") (pintype "bidirectional"))
      (node (ref "R7") (pin "1") (pinfunction "1_1") (pintype "passive"))
      (node (ref "TP7") (pin "TP") (pinfunction "TP_TP") (pintype "input"))
      (node (ref "U1") (pin "5") (pinfunction "DI(IO0)_5") (pintype "bidirectional"))
      (node (ref "U2") (pin "7") (pinfunction "IO7_7") (pintype "bidirectional"))
    )
    (net (code "21") (name "Net-(CHG_LED-PadC)") (class "Default")
      (node (ref "CHG_LED") (pin "C") (pinfunction "C_C") (pintype "passive"))
      (node (ref "R1_BAT") (pin "1") (pinfunction "1_1") (pintype "passive"))
    )
    (net (code "22") (name "Net-(D2-CATHODE)") (class "Default")
      (node (ref "C1_BAT1") (pin "1") (pinfunction "1_1") (pintype "passive"))
      (node (ref "D2") (pin "1") (pinfunction "CATHODE_1") (pintype "bidirectional"))
      (node (ref "IC4") (pin "1") (pinfunction "VIN_1") (pintype "bidirectional"))
      (node (ref "IC4") (pin "3") (pinfunction "CE_3") (pintype "bidirectional"))
      (node (ref "Q1") (pin "2") (pinfunction "S_2") (pintype "bidirectional"))
    )
    (net (code "23") (name "Net-(D3-A)") (class "Default")
      (node (ref "C4") (pin "1") (pinfunction "1_1") (pintype "passive"))
      (node (ref "D3") (pin "2") (pinfunction "A_2") (pintype "bidirectional"))
      (node (ref "D4") (pin "1") (pinfunction "K_1") (pintype "bidirectional"))
    )
    (net (code "24") (name "Net-(D7-CATHODE)") (class "Default")
      (node (ref "D7") (pin "1") (pinfunction "CATHODE_1") (pintype "bidirectional"))
      (node (ref "R_CAPACITOR") (pin "1") (pinfunction "1_1") (pintype "passive"))
    )
    (net (code "25") (name "Net-(EPD_C1-Pad2)") (class "Default")
      (node (ref "EPD_C1") (pin "2") (pinfunction "2_2") (pintype "passive"))
      (node (ref "J1") (pin "4") (pinfunction "4_4") (pintype "bidirectional"))
    )
    (net (code "26") (name "Net-(EPD_C2-Pad2)") (class "Default")
      (node (ref "EPD_C2") (pin "2") (pinfunction "2_2") (pintype "passive"))
      (node (ref "J1") (pin "5") (pinfunction "5_5") (pintype "bidirectional"))
    )
    (net (code "27") (name "Net-(EPD_C6-Pad2)") (class "Default")
      (node (ref "EPD_C6") (pin "2") (pinfunction "2_2") (pintype "passive"))
      (node (ref "J1") (pin "18") (pinfunction "18_18") (pintype "bidirectional"))
    )
    (net (code "28") (name "Net-(EPD_C7-Pad2)") (class "Default")
      (node (ref "EPD_C7") (pin "2") (pinfunction "2_2") (pintype "passive"))
      (node (ref "J1") (pin "19") (pinfunction "19_19") (pintype "bidirectional"))
    )
    (net (code "29") (name "Net-(EPD_C8-Pad2)") (class "Default")
      (node (ref "EPD_C8") (pin "2") (pinfunction "2_2") (pintype "passive"))
      (node (ref "J1") (pin "20") (pinfunction "20_20") (pintype "bidirectional"))
    )
    (net (code "30") (name "Net-(EPD_C10-Pad2)") (class "Default")
      (node (ref "EPD_C10") (pin "2") (pinfunction "2_2") (pintype "passive"))
      (node (ref "J1") (pin "22") (pinfunction "22_22") (pintype "bidirectional"))
    )
    (net (code "31") (name "Net-(EPD_C12-Pad2)") (class "Default")
      (node (ref "EPD_C12") (pin "2") (pinfunction "2_2") (pintype "passive"))
      (node (ref "J1") (pin "24") (pinfunction "24_24") (pintype "bidirectional"))
    )
    (net (code "32") (name "Net-(IC1-CT)") (class "Default")
      (node (ref "C_DELAY") (pin "1") (pinfunction "1_1") (pintype "passive"))
      (node (ref "IC1") (pin "5") (pinfunction "CT_5") (pintype "bidirectional"))
    )
    (net (code "33") (name "Net-(J2-PadA5)") (class "Default")
      (node (ref "J2") (pin "A5") (pinfunction "A5_A5") (pintype "bidirectional"))
      (node (ref "R2-USB1") (pin "2") (pinfunction "2_2") (pintype "passive"))
    )
    (net (code "34") (name "Net-(J2-PadB5)") (class "Default")
      (node (ref "J2") (pin "B5") (pinfunction "B5_B5") (pintype "bidirectional"))
      (node (ref "R2-USB") (pin "1") (pinfunction "1_1") (pintype "passive"))
    )
    (net (code "35") (name "Net-(MCP73831-PROG)") (class "Default")
      (node (ref "MCP73831") (pin "5") (pinfunction "PROG_5") (pintype "input"))
      (node (ref "R2_BAT") (pin "2") (pinfunction "2_2") (pintype "passive"))
    )
    (net (code "36") (name "Net-(MCP73831-STAT)") (class "Default")
      (node (ref "MCP73831") (pin "1") (pinfunction "STAT_1") (pintype "output"))
      (node (ref "R1_BAT") (pin "2") (pinfunction "2_2") (pintype "passive"))
    )
    (net (code "37") (name "PREVGH") (class "Default")
      (node (ref "D5") (pin "1") (pinfunction "K_1") (pintype "bidirectional"))
      (node (ref "EPD_C9") (pin "2") (pinfunction "2_2") (pintype "passive"))
      (node (ref "J1") (pin "21") (pinfunction "21_21") (pintype "bidirectional"))
    )
    (net (code "38") (name "PREVGL") (class "Default")
      (node (ref "D4") (pin "2") (pinfunction "A_2") (pintype "bidirectional"))
      (node (ref "EPD_C11") (pin "2") (pinfunction "2_2") (pintype "passive"))
      (node (ref "J1") (pin "23") (pinfunction "23_23") (pintype "bidirectional"))
    )
    (net (code "39") (name "RESE") (class "Default")
      (node (ref "J1") (pin "3") (pinfunction "3_3") (pintype "bidirectional"))
      (node (ref "Q3") (pin "2") (pinfunction "S_2") (pintype "bidirectional"))
      (node (ref "R3") (pin "2") (pinfunction "2_2") (pintype "passive"))
    )
    (net (code "40") (name "RESE'") (class "Default")
      (node (ref "R2") (pin "2") (pinfunction "2_2") (pintype "passive"))
      (node (ref "R3") (pin "1") (pinfunction "1_1") (pintype "passive"))
      (node (ref "SJ1") (pin "2") (pinfunction "2_2") (pintype "passive"))
    )
    (net (code "41") (name "RESET") (class "Default")
      (node (ref "C5") (pin "1") (pinfunction "1_1") (pintype "passive"))
      (node (ref "IC1") (pin "1") (pinfunction "VOUT_1") (pintype "bidirectional"))
      (node (ref "RESET_BUTTON") (pin "3") (pinfunction "3_3") (pintype "passive"))
      (node (ref "RESET_BUTTON") (pin "4") (pinfunction "4_4") (pintype "passive"))
      (node (ref "R_RESET") (pin "1") (pinfunction "1_1") (pintype "passive"))
      (node (ref "U2") (pin "3") (pinfunction "EN_3") (pintype "input"))
    )
    (net (code "42") (name "RTC_RST") (class "Default")
      (node (ref "U2") (pin "16") (pinfunction "IO18_16") (pintype "bidirectional"))
      (node (ref "U3") (pin "4") (pinfunction "~{RST}_4") (pintype "input"))
    )
    (net (code "43") (name "RX") (class "Default")
      (node (ref "TP2") (pin "TP") (pinfunction "TP_TP") (pintype "input"))
      (node (ref "U2") (pin "24") (pinfunction "RXD0/GPIO17_24") (pintype "bidirectional"))
    )
    (net (code "44") (name "SCK") (class "Default")
      (node (ref "D10") (pin "2") (pinfunction "2_2") (pintype "passive"))
      (node (ref "J1") (pin "13") (pinfunction "13_13") (pintype "bidirectional"))
      (node (ref "J4") (pin "P5") (pinfunction "CLK_P5") (pintype "bidirectional"))
      (node (ref "R6") (pin "1") (pinfunction "1_1") (pintype "passive"))
      (node (ref "TP8") (pin "TP") (pinfunction "TP_TP") (pintype "input"))
      (node (ref "U1") (pin "6") (pinfunction "CLK_6") (pintype "input"))
      (node (ref "U2") (pin "6") (pinfunction "IO6_6") (pintype "bidirectional"))
    )
    (net (code "45") (name "SCL") (class "Default")
      (node (ref "J3") (pin "4") (pinfunction "4_4") (pintype "passive"))
      (node (ref "R2_PINH") (pin "1") (pinfunction "1_1") (pintype "passive"))
      (node (ref "SENSOR2") (pin "4") (pinfunction "SCK_4") (pintype "input"))
      (node (ref "U2") (pin "20") (pinfunction "IO22_20") (pintype "bidirectional"))
      (node (ref "U3") (pin "16") (pinfunction "SCL_16") (pintype "input"))
      (node (ref "U4") (pin "7") (pinfunction "SCL_7") (pintype "input"))
    )
    (net (code "46") (name "SDA") (class "Default")
      (node (ref "J3") (pin "3") (pinfunction "3_3") (pintype "passive"))
      (node (ref "R1_PINH") (pin "1") (pinfunction "1_1") (pintype "passive"))
      (node (ref "SENSOR2") (pin "3") (pinfunction "SDI_3") (pintype "bidirectional"))
      (node (ref "U2") (pin "19") (pinfunction "IO21_19") (pintype "bidirectional"))
      (node (ref "U3") (pin "15") (pinfunction "SDA_15") (pintype "bidirectional"))
      (node (ref "U4") (pin "8") (pinfunction "SDA_8") (pintype "bidirectional"))
    )
    (net (code "47") (name "SRC") (class "Default")
      (node (ref "C4") (pin "2") (pinfunction "2_2") (pintype "passive"))
      (node (ref "D5") (pin "2") (pinfunction "A_2") (pintype "bidirectional"))
      (node (ref "L1") (pin "1") (pinfunction "1_1") (pintype "passive"))
      (node (ref "Q3") (pin "3") (pinfunction "D_3") (pintype "bidirectional"))
    )
    (net (code "48") (name "SS_SD") (class "Default")
      (node (ref "D8") (pin "2") (pinfunction "2_2") (pintype "passive"))
      (node (ref "J4") (pin "P2") (pinfunction "CD/DAT3_P2") (pintype "bidirectional"))
      (node (ref "R10") (pin "1") (pinfunction "1_1") (pintype "passive"))
      (node (ref "U2") (pin "4") (pinfunction "IO4_4") (pintype "bidirectional"))
    )
    (net (code "49") (name "TX") (class "Default")
      (node (ref "TP1") (pin "TP") (pinfunction "TP_TP") (pintype "input"))
      (node (ref "U2") (pin "25") (pinfunction "TXD0/GPIO16_25") (pintype "bidirectional"))
    )
    (net (code "50") (name "USB_D+") (class "Default")
      (node (ref "D1") (pin "1") (pinfunction "I/O1_1_1") (pintype "bidirectional"))
      (node (ref "U2") (pin "14") (pinfunction "IO13_14") (pintype "bidirectional"))
    )
    (net (code "51") (name "USB_D-") (class "Default")
      (node (ref "D1") (pin "3") (pinfunction "I/O2_1_3") (pintype "bidirectional"))
      (node (ref "U2") (pin "13") (pinfunction "IO12_13") (pintype "bidirectional"))
    )
    (net (code "52") (name "VBAT") (class "Default")
      (node (ref "C2_BAT") (pin "1") (pinfunction "1_1") (pintype "passive"))
      (node (ref "MCP73831") (pin "3") (pinfunction "VBAT_3") (pintype "power_in"))
      (node (ref "Q1") (pin "3") (pinfunction "D_3") (pintype "bidirectional"))
      (node (ref "TP3") (pin "TP") (pinfunction "TP_TP") (pintype "input"))
      (node (ref "U4") (pin "2") (pinfunction "CELL_2") (pintype "power_in"))
      (node (ref "U4") (pin "3") (pinfunction "VDD_3") (pintype "power_in"))
    )
    (net (code "53") (name "VBUS") (class "Default")
      (node (ref "C1_BAT") (pin "1") (pinfunction "1_1") (pintype "passive"))
      (node (ref "C4_USB") (pin "1") (pinfunction "1_1") (pintype "passive"))
      (node (ref "C5_USB") (pin "1") (pinfunction "1_1") (pintype "passive"))
      (node (ref "CHG_LED") (pin "A") (pinfunction "A_A") (pintype "passive"))
      (node (ref "D1") (pin "5") (pinfunction "VBUS_5") (pintype "bidirectional"))
      (node (ref "D2") (pin "2") (pinfunction "ANODE_2") (pintype "bidirectional"))
      (node (ref "MCP73831") (pin "4") (pinfunction "VIN_4") (pintype "power_in"))
      (node (ref "PFMF.050.1") (pin "2") (pinfunction "2_2") (pintype "passive"))
      (node (ref "Q1") (pin "1") (pinfunction "G_1") (pintype "bidirectional"))
      (node (ref "R1_PWRUSB") (pin "2") (pinfunction "2_2") (pintype "passive"))
      (node (ref "TP14") (pin "TP") (pinfunction "TP_TP") (pintype "input"))
    )
    (net (code "54") (name "VRTC") (class "Default")
      (node (ref "C10_SUPERCAP") (pin "2") (pinfunction "2_2") (pintype "passive"))
      (node (ref "C8") (pin "1") (pinfunction "1_1") (pintype "passive"))
      (node (ref "R_CAPACITOR") (pin "2") (pinfunction "2_2") (pintype "passive"))
      (node (ref "U3") (pin "14") (pinfunction "VBAT_14") (pintype "power_in"))
    )
    (net (code "55") (name "VUSB") (class "Default")
      (node (ref "J2") (pin "A4") (pinfunction "A4_A4") (pintype "bidirectional"))
      (node (ref "J2") (pin "A9") (pinfunction "A9_A9") (pintype "bidirectional"))
      (node (ref "J2") (pin "B4") (pinfunction "B4_B4") (pintype "bidirectional"))
      (node (ref "J2") (pin "B9") (pinfunction "B9_B9") (pintype "bidirectional"))
      (node (ref "PFMF.050.1") (pin "1") (pinfunction "1_1") (pintype "passive"))
    )
    (net (code "56") (name "unconnected-(IC1-NC-Pad4)") (class "Default")
      (node (ref "IC1") (pin "4") (pinfunction "NC_4") (pintype "no_connect"))
    )
    (net (code "57") (name "unconnected-(IC4-NC-Pad4)") (class "Default")
      (node (ref "IC4") (pin "4") (pinfunction "NC_4") (pintype "no_connect"))
    )
    (net (code "58") (name "unconnected-(J1-Pad1)") (class "Default")
      (node (ref "J1") (pin "1") (pinfunction "1_1") (pintype "bidirectional"))
    )
    (net (code "59") (name "unconnected-(J1-Pad6)") (class "Default")
      (node (ref "J1") (pin "6") (pinfunction "6_6") (pintype "bidirectional"))
    )
    (net (code "60") (name "unconnected-(J1-Pad7)") (class "Default")
      (node (ref "J1") (pin "7") (pinfunction "7_7") (pintype "bidirectional"))
    )
    (net (code "61") (name "unconnected-(J2-PadA8)") (class "Default")
      (node (ref "J2") (pin "A8") (pinfunction "A8_A8") (pintype "bidirectional"))
    )
    (net (code "62") (name "unconnected-(J2-PadB8)") (class "Default")
      (node (ref "J2") (pin "B8") (pinfunction "B8_B8") (pintype "bidirectional"))
    )
    (net (code "63") (name "unconnected-(J4-DAT1-PadP8)") (class "Default")
      (node (ref "J4") (pin "P8") (pinfunction "DAT1_P8") (pintype "bidirectional"))
    )
    (net (code "64") (name "unconnected-(J4-DAT2-PadP1)") (class "Default")
      (node (ref "J4") (pin "P1") (pinfunction "DAT2_P1") (pintype "bidirectional"))
    )
    (net (code "65") (name "unconnected-(J4-DETECTION_1-PadS1)") (class "Default")
      (node (ref "J4") (pin "S1") (pinfunction "DETECTION_1_S1") (pintype "bidirectional"))
    )
    (net (code "66") (name "unconnected-(J4-DETECTION_2-PadS2)") (class "Default")
      (node (ref "J4") (pin "S2") (pinfunction "DETECTION_2_S2") (pintype "bidirectional"))
    )
    (net (code "67") (name "unconnected-(U2-NC-Pad22)") (class "Default")
      (node (ref "U2") (pin "22") (pinfunction "NC_22") (pintype "no_connect"))
    )
    (net (code "68") (name "unconnected-(U4-~{ALERT}-Pad5)") (class "Default")
      (node (ref "U4") (pin "5") (pinfunction "~{ALERT}_5") (pintype "output"))
    )
  )
)
